# Schematic.net
KiCad netlist of a schematic drawn in Altium Designer
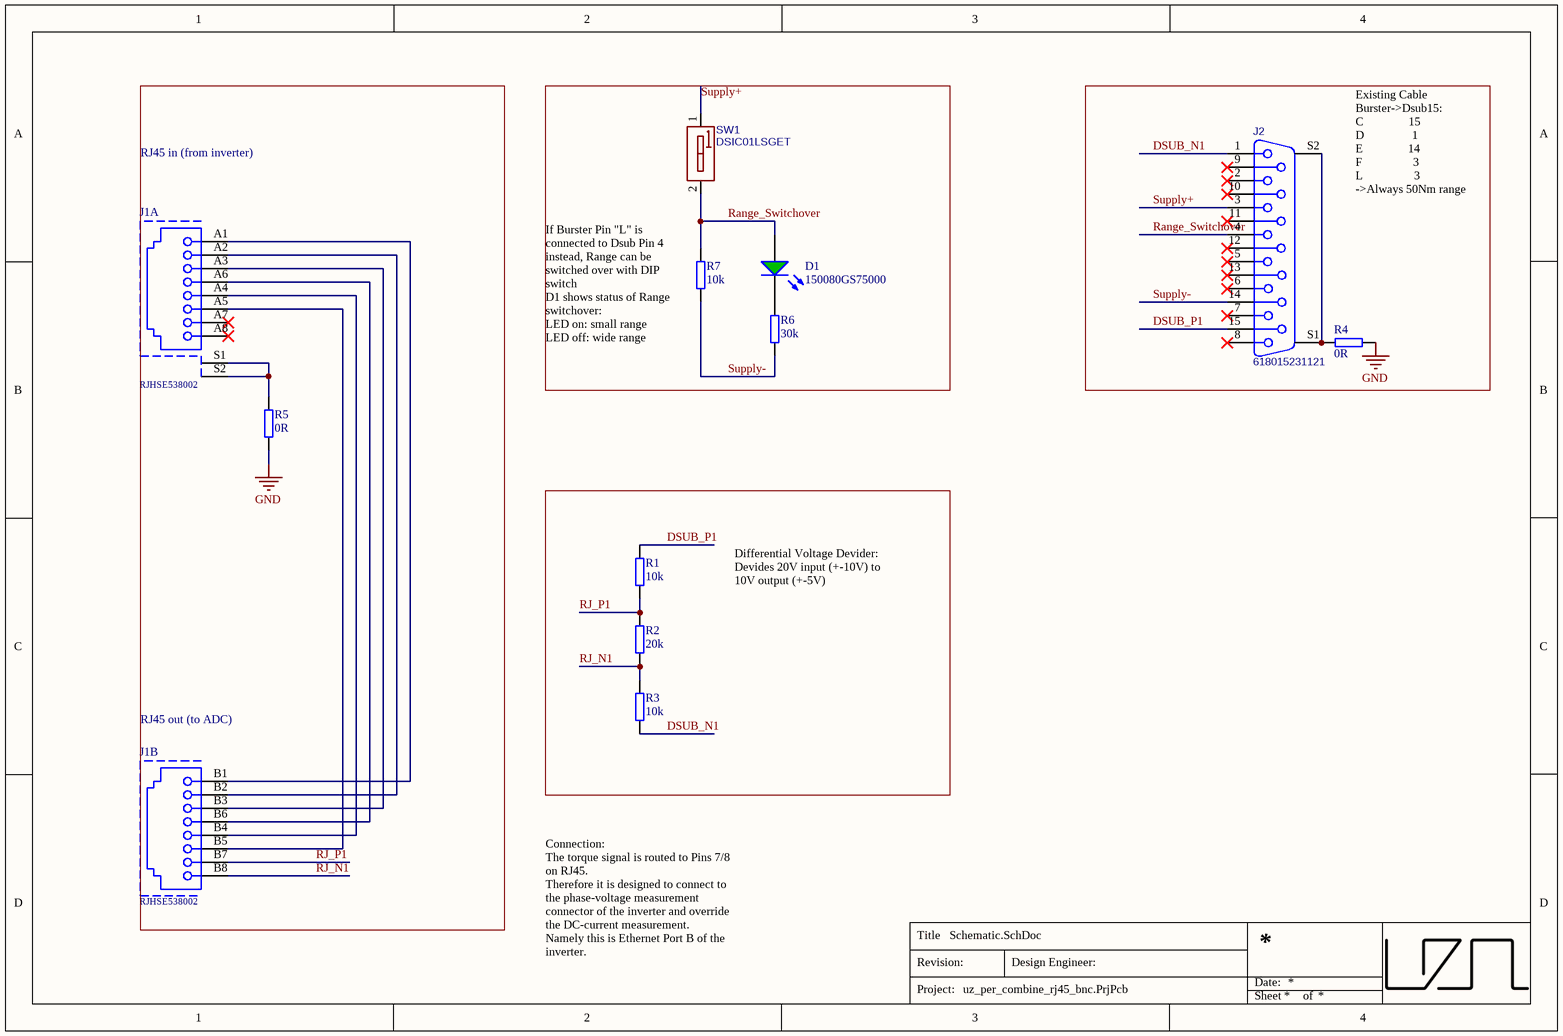
[diagram p0: Schematic.SchDoc]

(export (version "E")
  (design (tool "Eeschema 10.0.6"))
  (components
    (comp (ref "D1")
      (value "150080GS75000")
      (footprint "LEDM2012X80N")
      (description "WL-SMCW SMD Mono-color Chip LED Waterclear Green 0805")
      (fields
        (field (name "MANUFACTURER") "Wuerth Elektronik")
        (field (name "LCSC PART NUMBER") "C2297")
        (field (name "CREATED FROM") "MGremer")
      )
      (libsource (lib "user") (part "LED_Green"))
    )
    (comp (ref "J1")
      (value "RJHSE538002")
      (footprint "RJHSE-5380-02")
      (description "CAT5, RJ45 Connector, 1x2")
      (fields (field (name "MANUFACTURER") "Amphenol") (field (name "CREATED FROM") "MGremer"))
      (libsource (lib "user") (part "RJHSE-5380-02"))
    )
    (comp (ref "J2")
      (value "618015231121")
      (footprint "PCB - MISC - DSUB15")
      (description "15 Female D-Sub Shrouded 2 3A -40℃~+85℃ Plugin D-Sub/DVI/HDMI Connectors ROHS")
      (fields
        (field (name "MANUFACTURER") "Nextron(Nextronics Engineering)")
        (field (name "LCSC PART NUMBER") "C2846090")
        (field (name "CREATED FROM") "NDiringer")
      )
      (libsource (lib "user") (part "SUB-DRBF-607A-002"))
    )
    (comp (ref "R1")
      (value "10k")
      (footprint "RES 0805_2012")
      (description "SMD resistor 1%")
      (fields
        (field (name "MANUFACTURER PART NUMBER") "ERJ-6ENF1182V")
        (field (name "MANUFACTURER") "Panasonic")
        (field (name "CREATED FROM") "MGremer")
      )
      (libsource (lib "user") (part "Resistor"))
    )
    (comp (ref "R2")
      (value "20k")
      (footprint "RES 0805_2012")
      (description "SMD resistor 1%")
      (fields
        (field (name "MANUFACTURER PART NUMBER") "ERJ-6ENF1182V")
        (field (name "MANUFACTURER") "Panasonic")
        (field (name "CREATED FROM") "MGremer")
      )
      (libsource (lib "user") (part "Resistor"))
    )
    (comp (ref "R3")
      (value "10k")
      (footprint "RES 0805_2012")
      (description "SMD resistor 1%")
      (fields
        (field (name "MANUFACTURER PART NUMBER") "ERJ-6ENF1182V")
        (field (name "MANUFACTURER") "Panasonic")
        (field (name "CREATED FROM") "MGremer")
      )
      (libsource (lib "user") (part "Resistor"))
    )
    (comp (ref "R4")
      (value "0R")
      (footprint "RES 0805_2012")
      (description "SMD resistor 1%")
      (fields
        (field (name "MANUFACTURER PART NUMBER") "ERJ-6ENF1182V")
        (field (name "MANUFACTURER") "Panasonic")
        (field (name "CREATED FROM") "MGremer")
      )
      (libsource (lib "user") (part "Resistor"))
    )
    (comp (ref "R5")
      (value "0R")
      (footprint "RES 0805_2012")
      (description "SMD resistor 1%")
      (fields
        (field (name "MANUFACTURER PART NUMBER") "ERJ-6ENF1182V")
        (field (name "MANUFACTURER") "Panasonic")
        (field (name "CREATED FROM") "MGremer")
      )
      (libsource (lib "user") (part "Resistor"))
    )
    (comp (ref "R6")
      (value "30k")
      (footprint "RES 0805_2012")
      (description "SMD resistor 1%")
      (fields
        (field (name "MANUFACTURER PART NUMBER") "ERJ-6ENF1182V")
        (field (name "MANUFACTURER") "Panasonic")
        (field (name "CREATED FROM") "MGremer")
      )
      (libsource (lib "user") (part "Resistor"))
    )
    (comp (ref "R7")
      (value "10k")
      (footprint "RES 0805_2012")
      (description "SMD resistor 1%")
      (fields
        (field (name "MANUFACTURER PART NUMBER") "ERJ-6ENF1182V")
        (field (name "MANUFACTURER") "Panasonic")
        (field (name "CREATED FROM") "MGremer")
      )
      (libsource (lib "user") (part "Resistor"))
    )
    (comp (ref "SW1")
      (value "DSIC01LSGET")
      (footprint "SW-SMD_DSIC01LSGET")
      (description "SPST Black Flat dial, raised type 2.54mm 1 SMD DIP Switches")
      (fields
        (field (name "BOM_SUPPLIER PART") "C54948")
        (field (name "MANUFACTURER") "Dongguan Guangzhu Industrial")
        (field (name "CREATED FROM") "NDiringer")
      )
      (libsource (lib "user") (part "SCH - SWITCHES - DGI DSIC01LSGET"))
    )
  )
  (nets
    (net (code "1") (name "/DSUB_N1") (class "Default")
      (node (ref "J2") (pin "1") (pinfunction "1_1") (pintype "passive"))
      (node (ref "R3") (pin "1") (pinfunction "1_1") (pintype "passive"))
    )
    (net (code "2") (name "/DSUB_P1") (class "Default")
      (node (ref "J2") (pin "15") (pinfunction "15_15") (pintype "passive"))
      (node (ref "R1") (pin "2") (pinfunction "2_2") (pintype "passive"))
    )
    (net (code "3") (name "/RJ_N1") (class "Default")
      (node (ref "J1") (pin "B8") (pinfunction "B8_B8") (pintype "passive"))
      (node (ref "R2") (pin "1") (pinfunction "1_1") (pintype "passive"))
      (node (ref "R3") (pin "2") (pinfunction "2_2") (pintype "passive"))
    )
    (net (code "4") (name "/RJ_P1") (class "Default")
      (node (ref "J1") (pin "B7") (pinfunction "B7_B7") (pintype "passive"))
      (node (ref "R1") (pin "1") (pinfunction "1_1") (pintype "passive"))
      (node (ref "R2") (pin "2") (pinfunction "2_2") (pintype "passive"))
    )
    (net (code "5") (name "/Range_Switchover") (class "Default")
      (node (ref "D1") (pin "2") (pinfunction "A_2") (pintype "passive"))
      (node (ref "J2") (pin "4") (pinfunction "4_4") (pintype "passive"))
      (node (ref "R7") (pin "2") (pinfunction "2_2") (pintype "passive"))
      (node (ref "SW1") (pin "2") (pinfunction "A2_2") (pintype "passive"))
    )
    (net (code "6") (name "/Supply+") (class "Default")
      (node (ref "J2") (pin "3") (pinfunction "3_3") (pintype "passive"))
      (node (ref "SW1") (pin "1") (pinfunction "A1_1") (pintype "passive"))
    )
    (net (code "7") (name "/Supply-") (class "Default")
      (node (ref "J2") (pin "14") (pinfunction "14_14") (pintype "passive"))
      (node (ref "R6") (pin "1") (pinfunction "1_1") (pintype "passive"))
      (node (ref "R7") (pin "1") (pinfunction "1_1") (pintype "passive"))
    )
    (net (code "8") (name "GND") (class "Default")
      (node (ref "R4") (pin "2") (pinfunction "2_2") (pintype "passive"))
      (node (ref "R5") (pin "1") (pinfunction "1_1") (pintype "passive"))
    )
    (net (code "9") (name "Net-(D1-K)") (class "Default")
      (node (ref "D1") (pin "1") (pinfunction "K_1") (pintype "passive"))
      (node (ref "R6") (pin "2") (pinfunction "2_2") (pintype "passive"))
    )
    (net (code "10") (name "Net-(J1-PadA1)") (class "Default")
      (node (ref "J1") (pin "A1") (pinfunction "A1_A1") (pintype "passive"))
      (node (ref "J1") (pin "B1") (pinfunction "B1_B1") (pintype "passive"))
    )
    (net (code "11") (name "Net-(J1-PadA2)") (class "Default")
      (node (ref "J1") (pin "A2") (pinfunction "A2_A2") (pintype "passive"))
      (node (ref "J1") (pin "B2") (pinfunction "B2_B2") (pintype "passive"))
    )
    (net (code "12") (name "Net-(J1-PadA3)") (class "Default")
      (node (ref "J1") (pin "A3") (pinfunction "A3_A3") (pintype "passive"))
      (node (ref "J1") (pin "B3") (pinfunction "B3_B3") (pintype "passive"))
    )
    (net (code "13") (name "Net-(J1-PadA4)") (class "Default")
      (node (ref "J1") (pin "A4") (pinfunction "A4_A4") (pintype "passive"))
      (node (ref "J1") (pin "B4") (pinfunction "B4_B4") (pintype "passive"))
    )
    (net (code "14") (name "Net-(J1-PadA5)") (class "Default")
      (node (ref "J1") (pin "A5") (pinfunction "A5_A5") (pintype "passive"))
      (node (ref "J1") (pin "B5") (pinfunction "B5_B5") (pintype "passive"))
    )
    (net (code "15") (name "Net-(J1-PadA6)") (class "Default")
      (node (ref "J1") (pin "A6") (pinfunction "A6_A6") (pintype "passive"))
      (node (ref "J1") (pin "B6") (pinfunction "B6_B6") (pintype "passive"))
    )
    (net (code "16") (name "Net-(J1-PadS1)") (class "Default")
      (node (ref "J1") (pin "S1") (pinfunction "S1_S1") (pintype "passive"))
      (node (ref "J1") (pin "S2") (pinfunction "S2_S2") (pintype "passive"))
      (node (ref "R5") (pin "2") (pinfunction "2_2") (pintype "passive"))
    )
    (net (code "17") (name "Net-(J2-MH1)") (class "Default")
      (node (ref "J2") (pin "S1") (pinfunction "MH1_S1") (pintype "passive"))
      (node (ref "J2") (pin "S2") (pinfunction "MH2_S2") (pintype "passive"))
      (node (ref "R4") (pin "1") (pinfunction "1_1") (pintype "passive"))
    )
    (net (code "18") (name "unconnected-(J1-PadA7)") (class "Default")
      (node (ref "J1") (pin "A7") (pinfunction "A7_A7") (pintype "passive+no_connect"))
    )
    (net (code "19") (name "unconnected-(J1-PadA8)") (class "Default")
      (node (ref "J1") (pin "A8") (pinfunction "A8_A8") (pintype "passive+no_connect"))
    )
    (net (code "20") (name "unconnected-(J2-Pad2)") (class "Default")
      (node (ref "J2") (pin "2") (pinfunction "2_2") (pintype "passive+no_connect"))
    )
    (net (code "21") (name "unconnected-(J2-Pad5)") (class "Default")
      (node (ref "J2") (pin "5") (pinfunction "5_5") (pintype "passive+no_connect"))
    )
    (net (code "22") (name "unconnected-(J2-Pad6)") (class "Default")
      (node (ref "J2") (pin "6") (pinfunction "6_6") (pintype "passive+no_connect"))
    )
    (net (code "23") (name "unconnected-(J2-Pad7)") (class "Default")
      (node (ref "J2") (pin "7") (pinfunction "7_7") (pintype "passive+no_connect"))
    )
    (net (code "24") (name "unconnected-(J2-Pad8)") (class "Default")
      (node (ref "J2") (pin "8") (pinfunction "8_8") (pintype "passive+no_connect"))
    )
    (net (code "25") (name "unconnected-(J2-Pad9)") (class "Default")
      (node (ref "J2") (pin "9") (pinfunction "9_9") (pintype "passive+no_connect"))
    )
    (net (code "26") (name "unconnected-(J2-Pad10)") (class "Default")
      (node (ref "J2") (pin "10") (pinfunction "10_10") (pintype "passive+no_connect"))
    )
    (net (code "27") (name "unconnected-(J2-Pad11)") (class "Default")
      (node (ref "J2") (pin "11") (pinfunction "11_11") (pintype "passive+no_connect"))
    )
    (net (code "28") (name "unconnected-(J2-Pad12)") (class "Default")
      (node (ref "J2") (pin "12") (pinfunction "12_12") (pintype "passive+no_connect"))
    )
    (net (code "29") (name "unconnected-(J2-Pad13)") (class "Default")
      (node (ref "J2") (pin "13") (pinfunction "13_13") (pintype "passive+no_connect"))
    )
  )
)
